# leds.net
KiCad netlist of a schematic drawn in Altium Designer
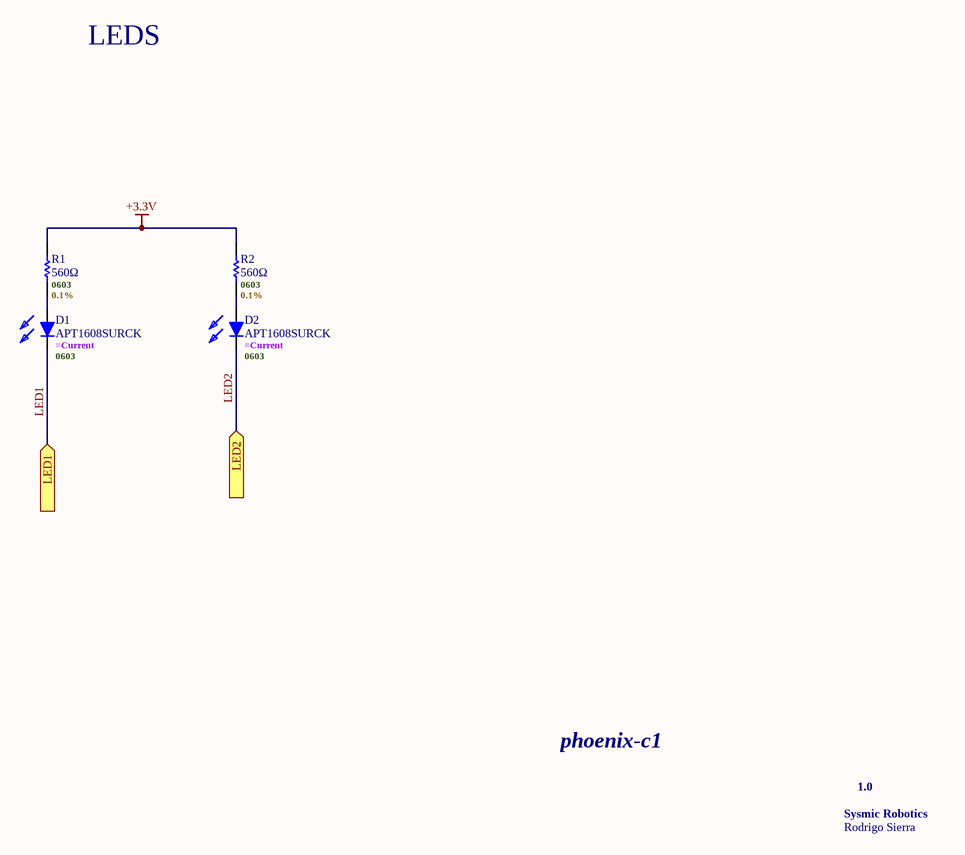
[diagram p0: leds.SchDoc]

(export (version "E")
  (design (tool "Eeschema 10.0.6"))
  (components
    (comp (ref "D1")
      (value "APT1608SURCK")
      (footprint "LED0603 - KINGBRIGHT")
      (description "APT1608SURCK Red Led, 630 Nm 1608 (0603) Clear, Rectangle Lens SMD Package")
      (fields (field (name "MANUFACTURER") "Kingbright") (field (name ".CASE/PACKAGE") "0603"))
      (libsource (lib "LED - APT1608SURCK") (part "APT1608SURCK"))
    )
    (comp (ref "D2")
      (value "APT1608SURCK")
      (footprint "LED0603 - KINGBRIGHT")
      (description "APT1608SURCK Red Led, 630 Nm 1608 (0603) Clear, Rectangle Lens SMD Package")
      (fields (field (name "MANUFACTURER") "Kingbright") (field (name ".CASE/PACKAGE") "0603"))
      (libsource (lib "LED - APT1608SURCK") (part "APT1608SURCK"))
    )
    (comp (ref "R1")
      (value "560Ω")
      (footprint "R0603 - YAGEO")
      (description "Res Thin Film 0603 560 Ohm 0.1% 0.1W(1/10W) ±25ppm/C Pad SMD T/R")
      (fields
        (field (name "MANUFACTURER") "Yageo Group")
        (field (name "MANUFACTURER PART NUMBER") "RT0603BRD07560RL")
        (field (name ".CASE/PACKAGE") "0603")
        (field (name ".TOLERANCE") "0.1%")
      )
      (libsource (lib "RES - RT0603BRD07560RL") (part "RT0603BRD07560RL"))
    )
    (comp (ref "R2")
      (value "560Ω")
      (footprint "R0603 - YAGEO")
      (description "Res Thin Film 0603 560 Ohm 0.1% 0.1W(1/10W) ±25ppm/C Pad SMD T/R")
      (fields
        (field (name "MANUFACTURER") "Yageo Group")
        (field (name "MANUFACTURER PART NUMBER") "RT0603BRD07560RL")
        (field (name ".CASE/PACKAGE") "0603")
        (field (name ".TOLERANCE") "0.1%")
      )
      (libsource (lib "RES - RT0603BRD07560RL") (part "RT0603BRD07560RL"))
    )
  )
  (nets
    (net (code "1") (name "+3.3V") (class "Default")
      (node (ref "R1") (pin "2") (pinfunction "2_2") (pintype "passive"))
      (node (ref "R2") (pin "2") (pinfunction "2_2") (pintype "passive"))
    )
    (net (code "2") (name "/LED1") (class "Default")
      (node (ref "D1") (pin "1") (pinfunction "1_1") (pintype "passive"))
    )
    (net (code "3") (name "/LED2") (class "Default")
      (node (ref "D2") (pin "1") (pinfunction "1_1") (pintype "passive"))
    )
    (net (code "4") (name "Net-(D1-Pad2)") (class "Default")
      (node (ref "D1") (pin "2") (pinfunction "2_2") (pintype "passive"))
      (node (ref "R1") (pin "1") (pinfunction "1_1") (pintype "passive"))
    )
    (net (code "5") (name "Net-(D2-Pad2)") (class "Default")
      (node (ref "D2") (pin "2") (pinfunction "2_2") (pintype "passive"))
      (node (ref "R2") (pin "1") (pinfunction "1_1") (pintype "passive"))
    )
  )
)
